# ledmatrix.net
KiCad netlist of a schematic drawn in EAGLE
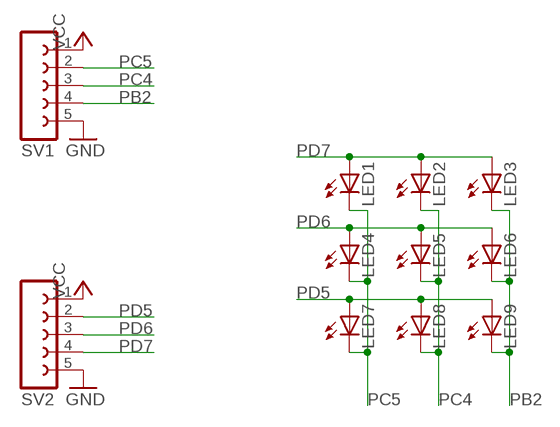
[diagram p0: schematic, sheet 1]

(export (version "E")
  (design (tool "Eeschema 10.0.6"))
  (components
    (comp (ref "LED1")
      (value "LED5MM")
      (footprint "eagle-import:LED5MM")
      (libsource (lib "eagle-import") (part "LED5MM"))
    )
    (comp (ref "LED2")
      (value "LED5MM")
      (footprint "eagle-import:LED5MM")
      (libsource (lib "eagle-import") (part "LED5MM"))
    )
    (comp (ref "LED3")
      (value "LED5MM")
      (footprint "eagle-import:LED5MM")
      (libsource (lib "eagle-import") (part "LED5MM"))
    )
    (comp (ref "LED4")
      (value "LED5MM")
      (footprint "eagle-import:LED5MM")
      (libsource (lib "eagle-import") (part "LED5MM"))
    )
    (comp (ref "LED5")
      (value "LED5MM")
      (footprint "eagle-import:LED5MM")
      (libsource (lib "eagle-import") (part "LED5MM"))
    )
    (comp (ref "LED6")
      (value "LED5MM")
      (footprint "eagle-import:LED5MM")
      (libsource (lib "eagle-import") (part "LED5MM"))
    )
    (comp (ref "LED7")
      (value "LED5MM")
      (footprint "eagle-import:LED5MM")
      (libsource (lib "eagle-import") (part "LED5MM"))
    )
    (comp (ref "LED8")
      (value "LED5MM")
      (footprint "eagle-import:LED5MM")
      (libsource (lib "eagle-import") (part "LED5MM"))
    )
    (comp (ref "LED9")
      (value "LED5MM")
      (footprint "eagle-import:LED5MM")
      (libsource (lib "eagle-import") (part "LED5MM"))
    )
    (comp (ref "SV1")
      (value "FE05-1")
      (footprint "eagle-import:FE05-1")
      (libsource (lib "eagle-import") (part "FE05-1"))
    )
    (comp (ref "SV2")
      (value "FE05-1")
      (footprint "eagle-import:FE05-1")
      (libsource (lib "eagle-import") (part "FE05-1"))
    )
  )
  (nets
    (net (code "1") (name "/PB2") (class "Default")
      (node (ref "LED3") (pin "K") (pinfunction "C_K") (pintype "passive"))
      (node (ref "LED6") (pin "K") (pinfunction "C_K") (pintype "passive"))
      (node (ref "LED9") (pin "K") (pinfunction "C_K") (pintype "passive"))
      (node (ref "SV1") (pin "4") (pinfunction "4_4") (pintype "passive"))
    )
    (net (code "2") (name "/PC4") (class "Default")
      (node (ref "LED2") (pin "K") (pinfunction "C_K") (pintype "passive"))
      (node (ref "LED5") (pin "K") (pinfunction "C_K") (pintype "passive"))
      (node (ref "LED8") (pin "K") (pinfunction "C_K") (pintype "passive"))
      (node (ref "SV1") (pin "3") (pinfunction "3_3") (pintype "passive"))
    )
    (net (code "3") (name "/PC5") (class "Default")
      (node (ref "LED1") (pin "K") (pinfunction "C_K") (pintype "passive"))
      (node (ref "LED4") (pin "K") (pinfunction "C_K") (pintype "passive"))
      (node (ref "LED7") (pin "K") (pinfunction "C_K") (pintype "passive"))
      (node (ref "SV1") (pin "2") (pinfunction "2_2") (pintype "passive"))
    )
    (net (code "4") (name "/PD5") (class "Default")
      (node (ref "LED7") (pin "A") (pinfunction "A_A") (pintype "passive"))
      (node (ref "LED8") (pin "A") (pinfunction "A_A") (pintype "passive"))
      (node (ref "LED9") (pin "A") (pinfunction "A_A") (pintype "passive"))
      (node (ref "SV2") (pin "2") (pinfunction "2_2") (pintype "passive"))
    )
    (net (code "5") (name "/PD6") (class "Default")
      (node (ref "LED4") (pin "A") (pinfunction "A_A") (pintype "passive"))
      (node (ref "LED5") (pin "A") (pinfunction "A_A") (pintype "passive"))
      (node (ref "LED6") (pin "A") (pinfunction "A_A") (pintype "passive"))
      (node (ref "SV2") (pin "3") (pinfunction "3_3") (pintype "passive"))
    )
    (net (code "6") (name "/PD7") (class "Default")
      (node (ref "LED1") (pin "A") (pinfunction "A_A") (pintype "passive"))
      (node (ref "LED2") (pin "A") (pinfunction "A_A") (pintype "passive"))
      (node (ref "LED3") (pin "A") (pinfunction "A_A") (pintype "passive"))
      (node (ref "SV2") (pin "4") (pinfunction "4_4") (pintype "passive"))
    )
    (net (code "7") (name "GND") (class "Default")
      (node (ref "SV1") (pin "5") (pinfunction "5_5") (pintype "passive"))
      (node (ref "SV2") (pin "5") (pinfunction "5_5") (pintype "passive"))
    )
    (net (code "8") (name "VCC") (class "Default")
      (node (ref "SV1") (pin "1") (pinfunction "1_1") (pintype "passive"))
      (node (ref "SV2") (pin "1") (pinfunction "1_1") (pintype "passive"))
    )
  )
)
